# warm-isolation-pcb-art.net
KiCad netlist of a schematic drawn in EAGLE
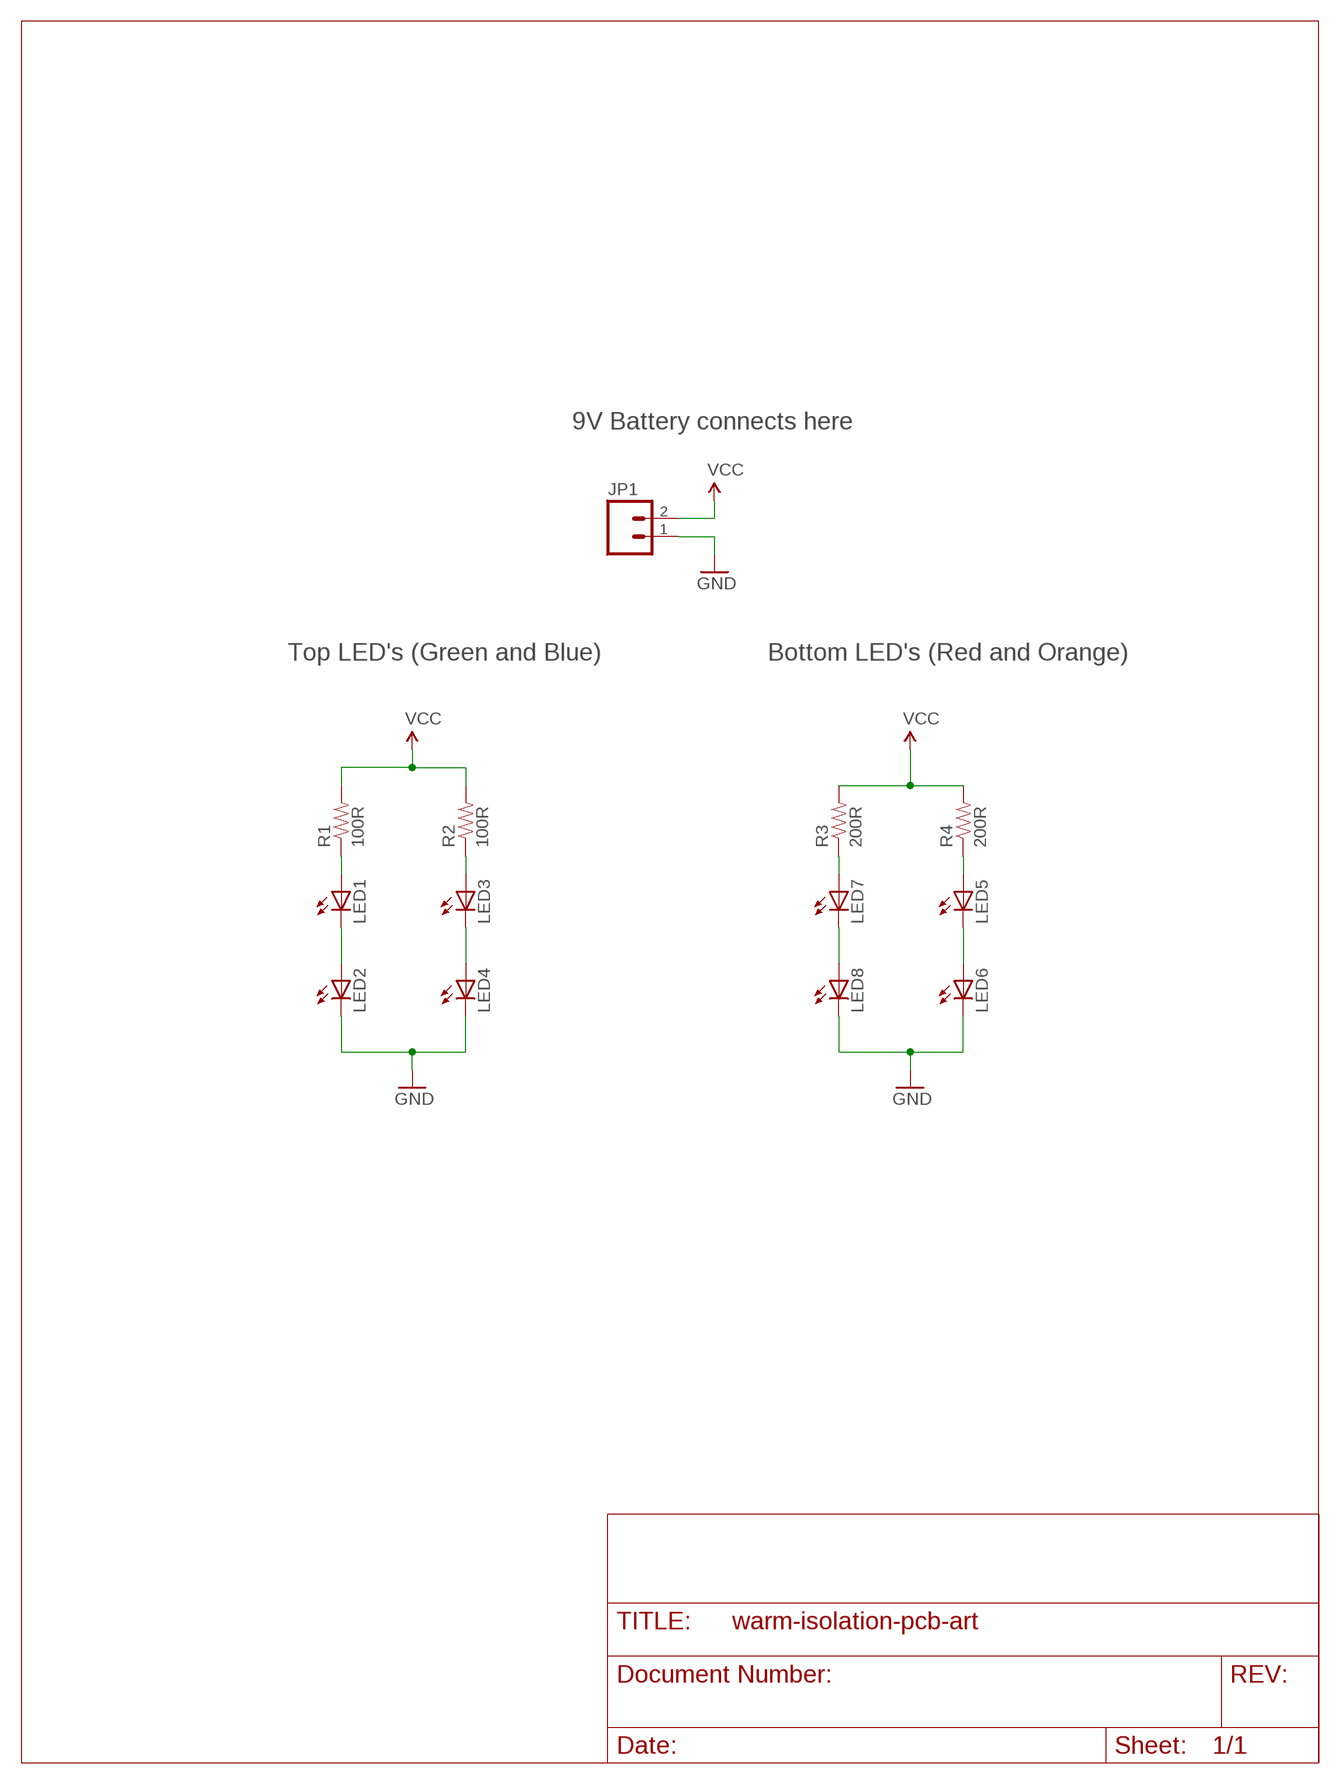
[diagram p0: schematic, sheet 1]

(export (version "E")
  (design (tool "Eeschema 10.0.6"))
  (components
    (comp (ref "JP1")
      (value "M02LOCK")
      (footprint "eagle-import:1X02_LOCK")
      (libsource (lib "eagle-import") (part "M02LOCK"))
    )
    (comp (ref "LED1")
      (value "LEDCHIP-LED0805")
      (footprint "eagle-import:CHIP-LED0805")
      (libsource (lib "eagle-import") (part "LEDCHIP-LED0805"))
    )
    (comp (ref "LED2")
      (value "LEDCHIP-LED0805")
      (footprint "eagle-import:CHIP-LED0805")
      (libsource (lib "eagle-import") (part "LEDCHIP-LED0805"))
    )
    (comp (ref "LED3")
      (value "LEDCHIP-LED0805")
      (footprint "eagle-import:CHIP-LED0805")
      (libsource (lib "eagle-import") (part "LEDCHIP-LED0805"))
    )
    (comp (ref "LED4")
      (value "LEDCHIP-LED0805")
      (footprint "eagle-import:CHIP-LED0805")
      (libsource (lib "eagle-import") (part "LEDCHIP-LED0805"))
    )
    (comp (ref "LED5")
      (value "LEDCHIP-LED0805")
      (footprint "eagle-import:CHIP-LED0805")
      (libsource (lib "eagle-import") (part "LEDCHIP-LED0805"))
    )
    (comp (ref "LED6")
      (value "LEDCHIP-LED0805")
      (footprint "eagle-import:CHIP-LED0805")
      (libsource (lib "eagle-import") (part "LEDCHIP-LED0805"))
    )
    (comp (ref "LED7")
      (value "LEDCHIP-LED0805")
      (footprint "eagle-import:CHIP-LED0805")
      (libsource (lib "eagle-import") (part "LEDCHIP-LED0805"))
    )
    (comp (ref "LED8")
      (value "LEDCHIP-LED0805")
      (footprint "eagle-import:CHIP-LED0805")
      (libsource (lib "eagle-import") (part "LEDCHIP-LED0805"))
    )
    (comp (ref "R1")
      (value "100R")
      (footprint "eagle-import:0805")
      (libsource (lib "eagle-import") (part "RESISTOR0805-RES"))
    )
    (comp (ref "R2")
      (value "100R")
      (footprint "eagle-import:0805")
      (libsource (lib "eagle-import") (part "RESISTOR0805-RES"))
    )
    (comp (ref "R3")
      (value "200R")
      (footprint "eagle-import:0805")
      (libsource (lib "eagle-import") (part "RESISTOR0805-RES"))
    )
    (comp (ref "R4")
      (value "200R")
      (footprint "eagle-import:0805")
      (libsource (lib "eagle-import") (part "RESISTOR0805-RES"))
    )
  )
  (nets
    (net (code "1") (name "GND") (class "Default")
      (node (ref "JP1") (pin "1") (pinfunction "1_1") (pintype "passive"))
      (node (ref "LED2") (pin "C") (pinfunction "C_C") (pintype "passive"))
      (node (ref "LED4") (pin "C") (pinfunction "C_C") (pintype "passive"))
      (node (ref "LED6") (pin "C") (pinfunction "C_C") (pintype "passive"))
      (node (ref "LED8") (pin "C") (pinfunction "C_C") (pintype "passive"))
    )
    (net (code "2") (name "Net-(LED1-PadA)") (class "Default")
      (node (ref "LED1") (pin "A") (pinfunction "A_A") (pintype "passive"))
      (node (ref "R1") (pin "1") (pinfunction "1_1") (pintype "passive"))
    )
    (net (code "3") (name "Net-(LED1-PadC)") (class "Default")
      (node (ref "LED1") (pin "C") (pinfunction "C_C") (pintype "passive"))
      (node (ref "LED2") (pin "A") (pinfunction "A_A") (pintype "passive"))
    )
    (net (code "4") (name "Net-(LED3-PadA)") (class "Default")
      (node (ref "LED3") (pin "A") (pinfunction "A_A") (pintype "passive"))
      (node (ref "R2") (pin "1") (pinfunction "1_1") (pintype "passive"))
    )
    (net (code "5") (name "Net-(LED3-PadC)") (class "Default")
      (node (ref "LED3") (pin "C") (pinfunction "C_C") (pintype "passive"))
      (node (ref "LED4") (pin "A") (pinfunction "A_A") (pintype "passive"))
    )
    (net (code "6") (name "Net-(LED5-PadA)") (class "Default")
      (node (ref "LED5") (pin "A") (pinfunction "A_A") (pintype "passive"))
      (node (ref "R4") (pin "1") (pinfunction "1_1") (pintype "passive"))
    )
    (net (code "7") (name "Net-(LED5-PadC)") (class "Default")
      (node (ref "LED5") (pin "C") (pinfunction "C_C") (pintype "passive"))
      (node (ref "LED6") (pin "A") (pinfunction "A_A") (pintype "passive"))
    )
    (net (code "8") (name "Net-(LED7-PadA)") (class "Default")
      (node (ref "LED7") (pin "A") (pinfunction "A_A") (pintype "passive"))
      (node (ref "R3") (pin "1") (pinfunction "1_1") (pintype "passive"))
    )
    (net (code "9") (name "Net-(LED7-PadC)") (class "Default")
      (node (ref "LED7") (pin "C") (pinfunction "C_C") (pintype "passive"))
      (node (ref "LED8") (pin "A") (pinfunction "A_A") (pintype "passive"))
    )
    (net (code "10") (name "VCC") (class "Default")
      (node (ref "JP1") (pin "2") (pinfunction "2_2") (pintype "passive"))
      (node (ref "R1") (pin "2") (pinfunction "2_2") (pintype "passive"))
      (node (ref "R2") (pin "2") (pinfunction "2_2") (pintype "passive"))
      (node (ref "R3") (pin "2") (pinfunction "2_2") (pintype "passive"))
      (node (ref "R4") (pin "2") (pinfunction "2_2") (pintype "passive"))
    )
  )
)
